# Rear_left_lamp_v1.net
KiCad netlist of a schematic drawn in EAGLE
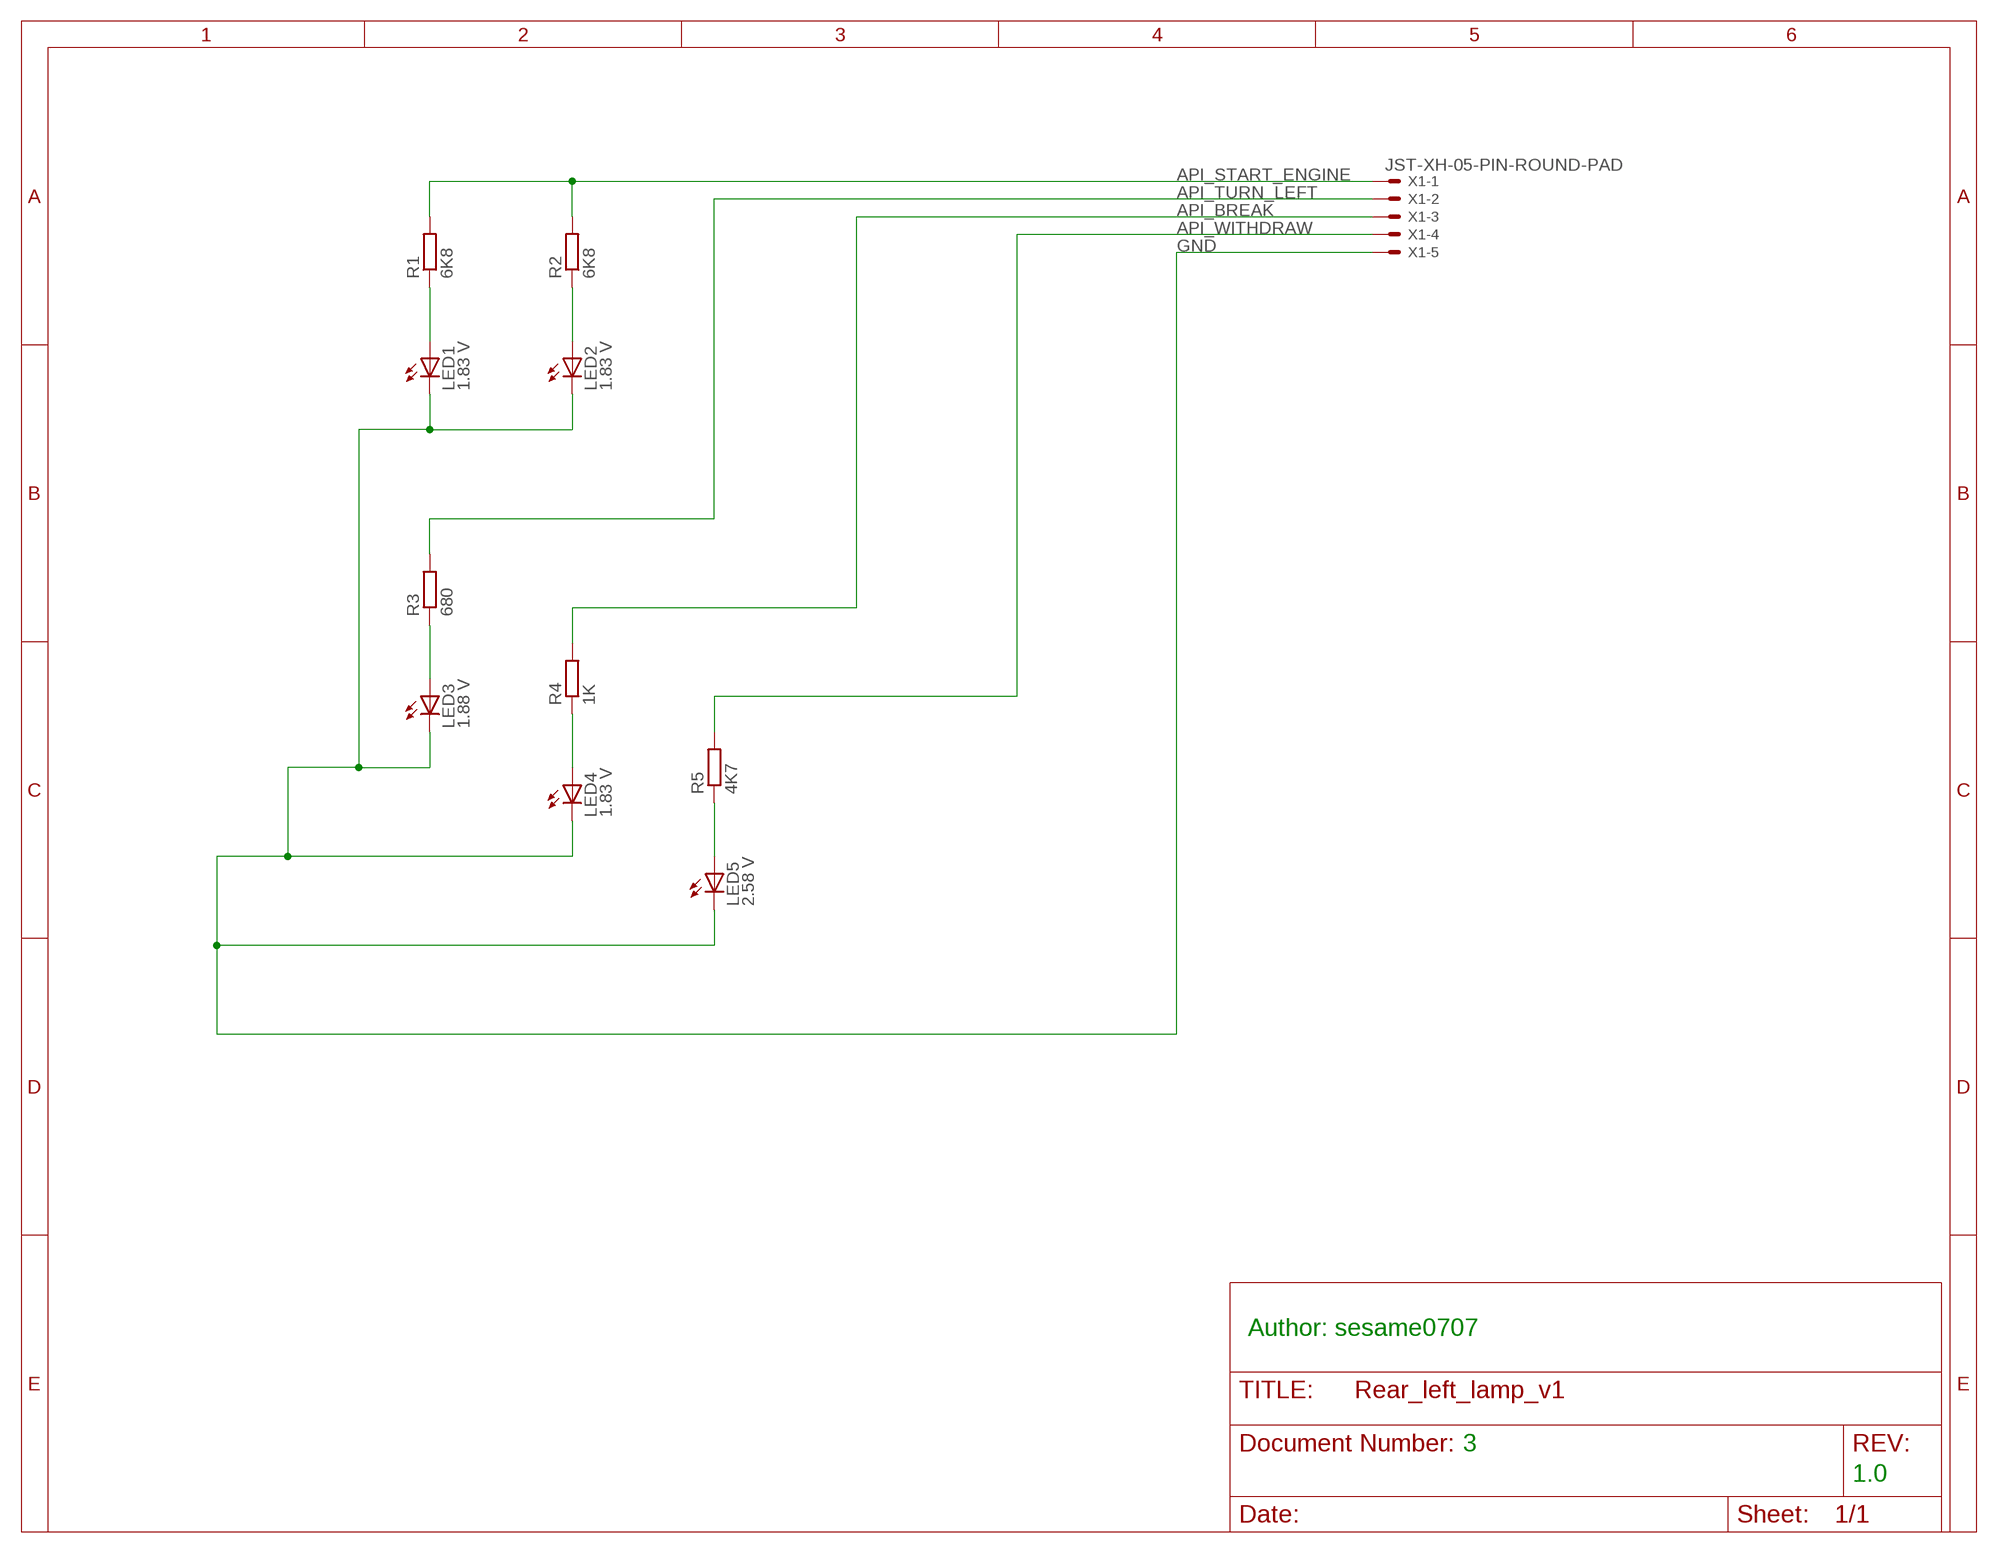
[diagram p0: schematic, sheet 1]

(export (version "E")
  (design (tool "Eeschema 10.0.6"))
  (components
    (comp (ref "LED1")
      (value "1.83 V")
      (footprint "eagle-import:LED5MM")
      (libsource (lib "eagle-import") (part "LED5MM"))
    )
    (comp (ref "LED2")
      (value "1.83 V")
      (footprint "eagle-import:LED5MM")
      (libsource (lib "eagle-import") (part "LED5MM"))
    )
    (comp (ref "LED3")
      (value "1.88 V")
      (footprint "eagle-import:LED5MM")
      (libsource (lib "eagle-import") (part "LED5MM"))
    )
    (comp (ref "LED4")
      (value "1.83 V")
      (footprint "eagle-import:LED5MM")
      (libsource (lib "eagle-import") (part "LED5MM"))
    )
    (comp (ref "LED5")
      (value "2.58 V")
      (footprint "eagle-import:LED5MM")
      (libsource (lib "eagle-import") (part "LED5MM"))
    )
    (comp (ref "R1")
      (value "6K8")
      (footprint "eagle-import:0204V")
      (libsource (lib "eagle-import") (part "R-EU_0204/2V"))
    )
    (comp (ref "R2")
      (value "6K8")
      (footprint "eagle-import:0204V")
      (libsource (lib "eagle-import") (part "R-EU_0204/2V"))
    )
    (comp (ref "R3")
      (value "680")
      (footprint "eagle-import:0204V")
      (libsource (lib "eagle-import") (part "R-EU_0204/2V"))
    )
    (comp (ref "R4")
      (value "1K")
      (footprint "eagle-import:0204V")
      (libsource (lib "eagle-import") (part "R-EU_0204/2V"))
    )
    (comp (ref "R5")
      (value "4K7")
      (footprint "eagle-import:0204V")
      (libsource (lib "eagle-import") (part "R-EU_0204/2V"))
    )
    (comp (ref "X1")
      (value "JST-XH-05-PIN-ROUND-PAD")
      (footprint "eagle-import:JST-XH-05-PACKAGE-ROUND-PAD")
      (libsource (lib "eagle-import") (part "JST-XH-05-PIN-ROUND-PAD"))
    )
  )
  (nets
    (net (code "1") (name "/API_BREAK") (class "Default")
      (node (ref "R4") (pin "2") (pinfunction "2_2") (pintype "passive"))
      (node (ref "X1") (pin "3") (pinfunction "S_3") (pintype "passive"))
    )
    (net (code "2") (name "/API_START_ENGINE") (class "Default")
      (node (ref "R1") (pin "2") (pinfunction "2_2") (pintype "passive"))
      (node (ref "R2") (pin "2") (pinfunction "2_2") (pintype "passive"))
      (node (ref "X1") (pin "1") (pinfunction "S_1") (pintype "passive"))
    )
    (net (code "3") (name "/API_TURN_LEFT") (class "Default")
      (node (ref "R3") (pin "2") (pinfunction "2_2") (pintype "passive"))
      (node (ref "X1") (pin "2") (pinfunction "S_2") (pintype "passive"))
    )
    (net (code "4") (name "/API_WITHDRAW") (class "Default")
      (node (ref "R5") (pin "2") (pinfunction "2_2") (pintype "passive"))
      (node (ref "X1") (pin "4") (pinfunction "S_4") (pintype "passive"))
    )
    (net (code "5") (name "/GND") (class "Default")
      (node (ref "LED1") (pin "K") (pinfunction "C_K") (pintype "passive"))
      (node (ref "LED2") (pin "K") (pinfunction "C_K") (pintype "passive"))
      (node (ref "LED3") (pin "K") (pinfunction "C_K") (pintype "passive"))
      (node (ref "LED4") (pin "K") (pinfunction "C_K") (pintype "passive"))
      (node (ref "LED5") (pin "K") (pinfunction "C_K") (pintype "passive"))
      (node (ref "X1") (pin "5") (pinfunction "S_5") (pintype "passive"))
    )
    (net (code "6") (name "Net-(LED1-PadA)") (class "Default")
      (node (ref "LED1") (pin "A") (pinfunction "A_A") (pintype "passive"))
      (node (ref "R1") (pin "1") (pinfunction "1_1") (pintype "passive"))
    )
    (net (code "7") (name "Net-(LED2-PadA)") (class "Default")
      (node (ref "LED2") (pin "A") (pinfunction "A_A") (pintype "passive"))
      (node (ref "R2") (pin "1") (pinfunction "1_1") (pintype "passive"))
    )
    (net (code "8") (name "Net-(LED3-PadA)") (class "Default")
      (node (ref "LED3") (pin "A") (pinfunction "A_A") (pintype "passive"))
      (node (ref "R3") (pin "1") (pinfunction "1_1") (pintype "passive"))
    )
    (net (code "9") (name "Net-(LED4-PadA)") (class "Default")
      (node (ref "LED4") (pin "A") (pinfunction "A_A") (pintype "passive"))
      (node (ref "R4") (pin "1") (pinfunction "1_1") (pintype "passive"))
    )
    (net (code "10") (name "Net-(LED5-PadA)") (class "Default")
      (node (ref "LED5") (pin "A") (pinfunction "A_A") (pintype "passive"))
      (node (ref "R5") (pin "1") (pinfunction "1_1") (pintype "passive"))
    )
  )
)
